# Sensors.net
KiCad netlist of a schematic drawn in EAGLE
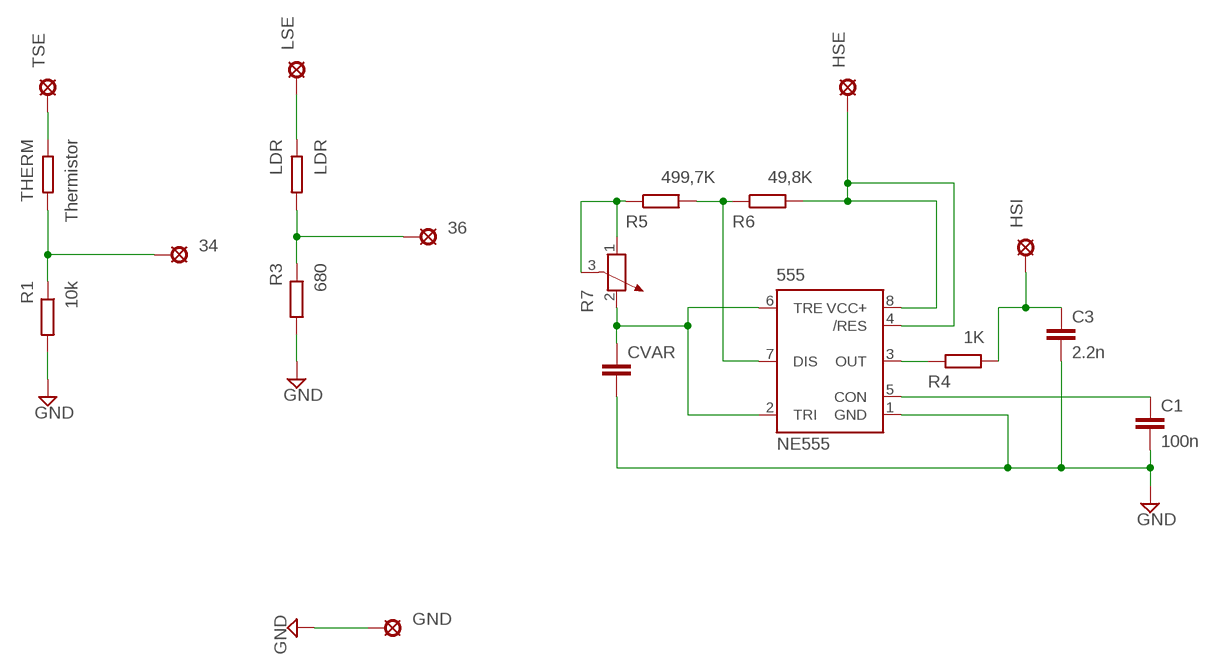
[diagram p0: schematic, sheet 1]

(export (version "E")
  (design (tool "Eeschema 10.0.6"))
  (components
    (comp (ref "34")
      (value "SE13")
      (footprint "eagle-import:SE13")
      (libsource (lib "eagle-import") (part "SE13"))
    )
    (comp (ref "36")
      (value "36")
      (footprint "eagle-import:SE13")
      (libsource (lib "eagle-import") (part "SE13"))
    )
    (comp (ref "555")
      (value "NE555")
      (footprint "eagle-import:DIL-08")
      (fields (field (name "MF") "Arrow Electronics") (field (name "MPN") "NE555N"))
      (libsource (lib "eagle-import") (part "NE555"))
    )
    (comp (ref "C1")
      (value "100n")
      (footprint "eagle-import:C0805")
      (libsource (lib "eagle-import") (part "C-EUC0805"))
    )
    (comp (ref "C3")
      (value "2.2n")
      (footprint "eagle-import:C0805")
      (libsource (lib "eagle-import") (part "C-EUC0805"))
    )
    (comp (ref "CVAR")
      (value "C-EU050-025X075")
      (footprint "eagle-import:C050-025X075")
      (libsource (lib "eagle-import") (part "C-EU050-025X075"))
    )
    (comp (ref "GND")
      (value "SE13")
      (footprint "eagle-import:SE13")
      (libsource (lib "eagle-import") (part "SE13"))
    )
    (comp (ref "HSE")
      (value "SE13")
      (footprint "eagle-import:SE13")
      (libsource (lib "eagle-import") (part "SE13"))
    )
    (comp (ref "HSI")
      (value "SE13")
      (footprint "eagle-import:SE13")
      (libsource (lib "eagle-import") (part "SE13"))
    )
    (comp (ref "LDR")
      (value "LDR")
      (footprint "eagle-import:WEERSTAND")
      (libsource (lib "eagle-import") (part "WEERSTAND"))
    )
    (comp (ref "LSE")
      (value "SE13")
      (footprint "eagle-import:SE13")
      (libsource (lib "eagle-import") (part "SE13"))
    )
    (comp (ref "R1")
      (value "10k")
      (footprint "eagle-import:R0805")
      (libsource (lib "eagle-import") (part "R-EU_R0805"))
    )
    (comp (ref "R3")
      (value "680")
      (footprint "eagle-import:R0805")
      (fields (field (name "SPICEPREFIX") "R"))
      (libsource (lib "eagle-import") (part "R-EU_R0805"))
    )
    (comp (ref "R4")
      (value "1K")
      (footprint "eagle-import:R0805")
      (libsource (lib "eagle-import") (part "R-EU_R0805"))
    )
    (comp (ref "R5")
      (value "499,7K")
      (footprint "eagle-import:R0805")
      (libsource (lib "eagle-import") (part "R-EU_R0805"))
    )
    (comp (ref "R6")
      (value "49,8K")
      (footprint "eagle-import:R0805")
      (libsource (lib "eagle-import") (part "R-EU_R0805"))
    )
    (comp (ref "R7")
      (value "POTENTIOMETER_PT-10")
      (footprint "eagle-import:PT-10")
      (libsource (lib "eagle-import") (part "POTENTIOMETER_PT-10"))
    )
    (comp (ref "THERM")
      (value "Thermistor")
      (footprint "eagle-import:WEERSTAND")
      (libsource (lib "eagle-import") (part "WEERSTAND"))
    )
    (comp (ref "TSE")
      (value "SE13")
      (footprint "eagle-import:SE13")
      (libsource (lib "eagle-import") (part "SE13"))
    )
  )
  (nets
    (net (code "1") (name "GND") (class "Default")
      (node (ref "555") (pin "1") (pinfunction "GND_1") (pintype "power_in"))
      (node (ref "C1") (pin "2") (pinfunction "2_2") (pintype "passive"))
      (node (ref "C3") (pin "2") (pinfunction "2_2") (pintype "passive"))
      (node (ref "CVAR") (pin "2") (pinfunction "2_2") (pintype "passive"))
      (node (ref "GND") (pin "MP") (pinfunction "MP_MP") (pintype "passive"))
      (node (ref "R1") (pin "2") (pinfunction "2_2") (pintype "passive"))
      (node (ref "R3") (pin "2") (pinfunction "2_2") (pintype "passive"))
    )
    (net (code "2") (name "Net-(555-CON)") (class "Default")
      (node (ref "555") (pin "5") (pinfunction "CON_5") (pintype "input"))
      (node (ref "C1") (pin "1") (pinfunction "1_1") (pintype "passive"))
    )
    (net (code "3") (name "Net-(555-DIS)") (class "Default")
      (node (ref "555") (pin "7") (pinfunction "DIS_7") (pintype "input"))
      (node (ref "R5") (pin "2") (pinfunction "2_2") (pintype "passive"))
      (node (ref "R6") (pin "1") (pinfunction "1_1") (pintype "passive"))
    )
    (net (code "4") (name "Net-(555-OUT)") (class "Default")
      (node (ref "555") (pin "3") (pinfunction "OUT_3") (pintype "output"))
      (node (ref "R4") (pin "1") (pinfunction "1_1") (pintype "passive"))
    )
    (net (code "5") (name "Net-(555-TRE)") (class "Default")
      (node (ref "555") (pin "2") (pinfunction "TRI_2") (pintype "input"))
      (node (ref "555") (pin "6") (pinfunction "TRE_6") (pintype "input"))
      (node (ref "CVAR") (pin "1") (pinfunction "1_1") (pintype "passive"))
      (node (ref "R7") (pin "2") (pinfunction "2_2") (pintype "passive"))
    )
    (net (code "6") (name "Net-(555-VCC+)") (class "Default")
      (node (ref "555") (pin "4") (pinfunction "/RES_4") (pintype "input"))
      (node (ref "555") (pin "8") (pinfunction "VCC+_8") (pintype "power_in"))
      (node (ref "HSE") (pin "MP") (pinfunction "MP_MP") (pintype "passive"))
      (node (ref "R6") (pin "2") (pinfunction "2_2") (pintype "passive"))
    )
    (net (code "7") (name "Net-(C3-Pad1)") (class "Default")
      (node (ref "C3") (pin "1") (pinfunction "1_1") (pintype "passive"))
      (node (ref "HSI") (pin "MP") (pinfunction "MP_MP") (pintype "passive"))
      (node (ref "R4") (pin "2") (pinfunction "2_2") (pintype "passive"))
    )
    (net (code "8") (name "Net-(LDR-P$3)") (class "Default")
      (node (ref "LDR") (pin "P$1") (pinfunction "P$3_P$1") (pintype "bidirectional"))
      (node (ref "LSE") (pin "MP") (pinfunction "MP_MP") (pintype "passive"))
    )
    (net (code "9") (name "Net-(LDR-P$4)") (class "Default")
      (node (ref "36") (pin "MP") (pinfunction "MP_MP") (pintype "passive"))
      (node (ref "LDR") (pin "P$2") (pinfunction "P$4_P$2") (pintype "bidirectional"))
      (node (ref "R3") (pin "1") (pinfunction "1_1") (pintype "passive"))
    )
    (net (code "10") (name "Net-(R5-Pad1)") (class "Default")
      (node (ref "R5") (pin "1") (pinfunction "1_1") (pintype "passive"))
      (node (ref "R7") (pin "1") (pinfunction "1_1") (pintype "passive"))
      (node (ref "R7") (pin "3") (pinfunction "3_3") (pintype "passive"))
    )
    (net (code "11") (name "Net-(THERM-P$3)") (class "Default")
      (node (ref "THERM") (pin "P$1") (pinfunction "P$3_P$1") (pintype "bidirectional"))
      (node (ref "TSE") (pin "MP") (pinfunction "MP_MP") (pintype "passive"))
    )
    (net (code "12") (name "Net-(THERM-P$4)") (class "Default")
      (node (ref "34") (pin "MP") (pinfunction "MP_MP") (pintype "passive"))
      (node (ref "R1") (pin "1") (pinfunction "1_1") (pintype "passive"))
      (node (ref "THERM") (pin "P$2") (pinfunction "P$4_P$2") (pintype "bidirectional"))
    )
  )
)
